# 05pwr_input.net
KiCad netlist of a schematic drawn in Altium Designer
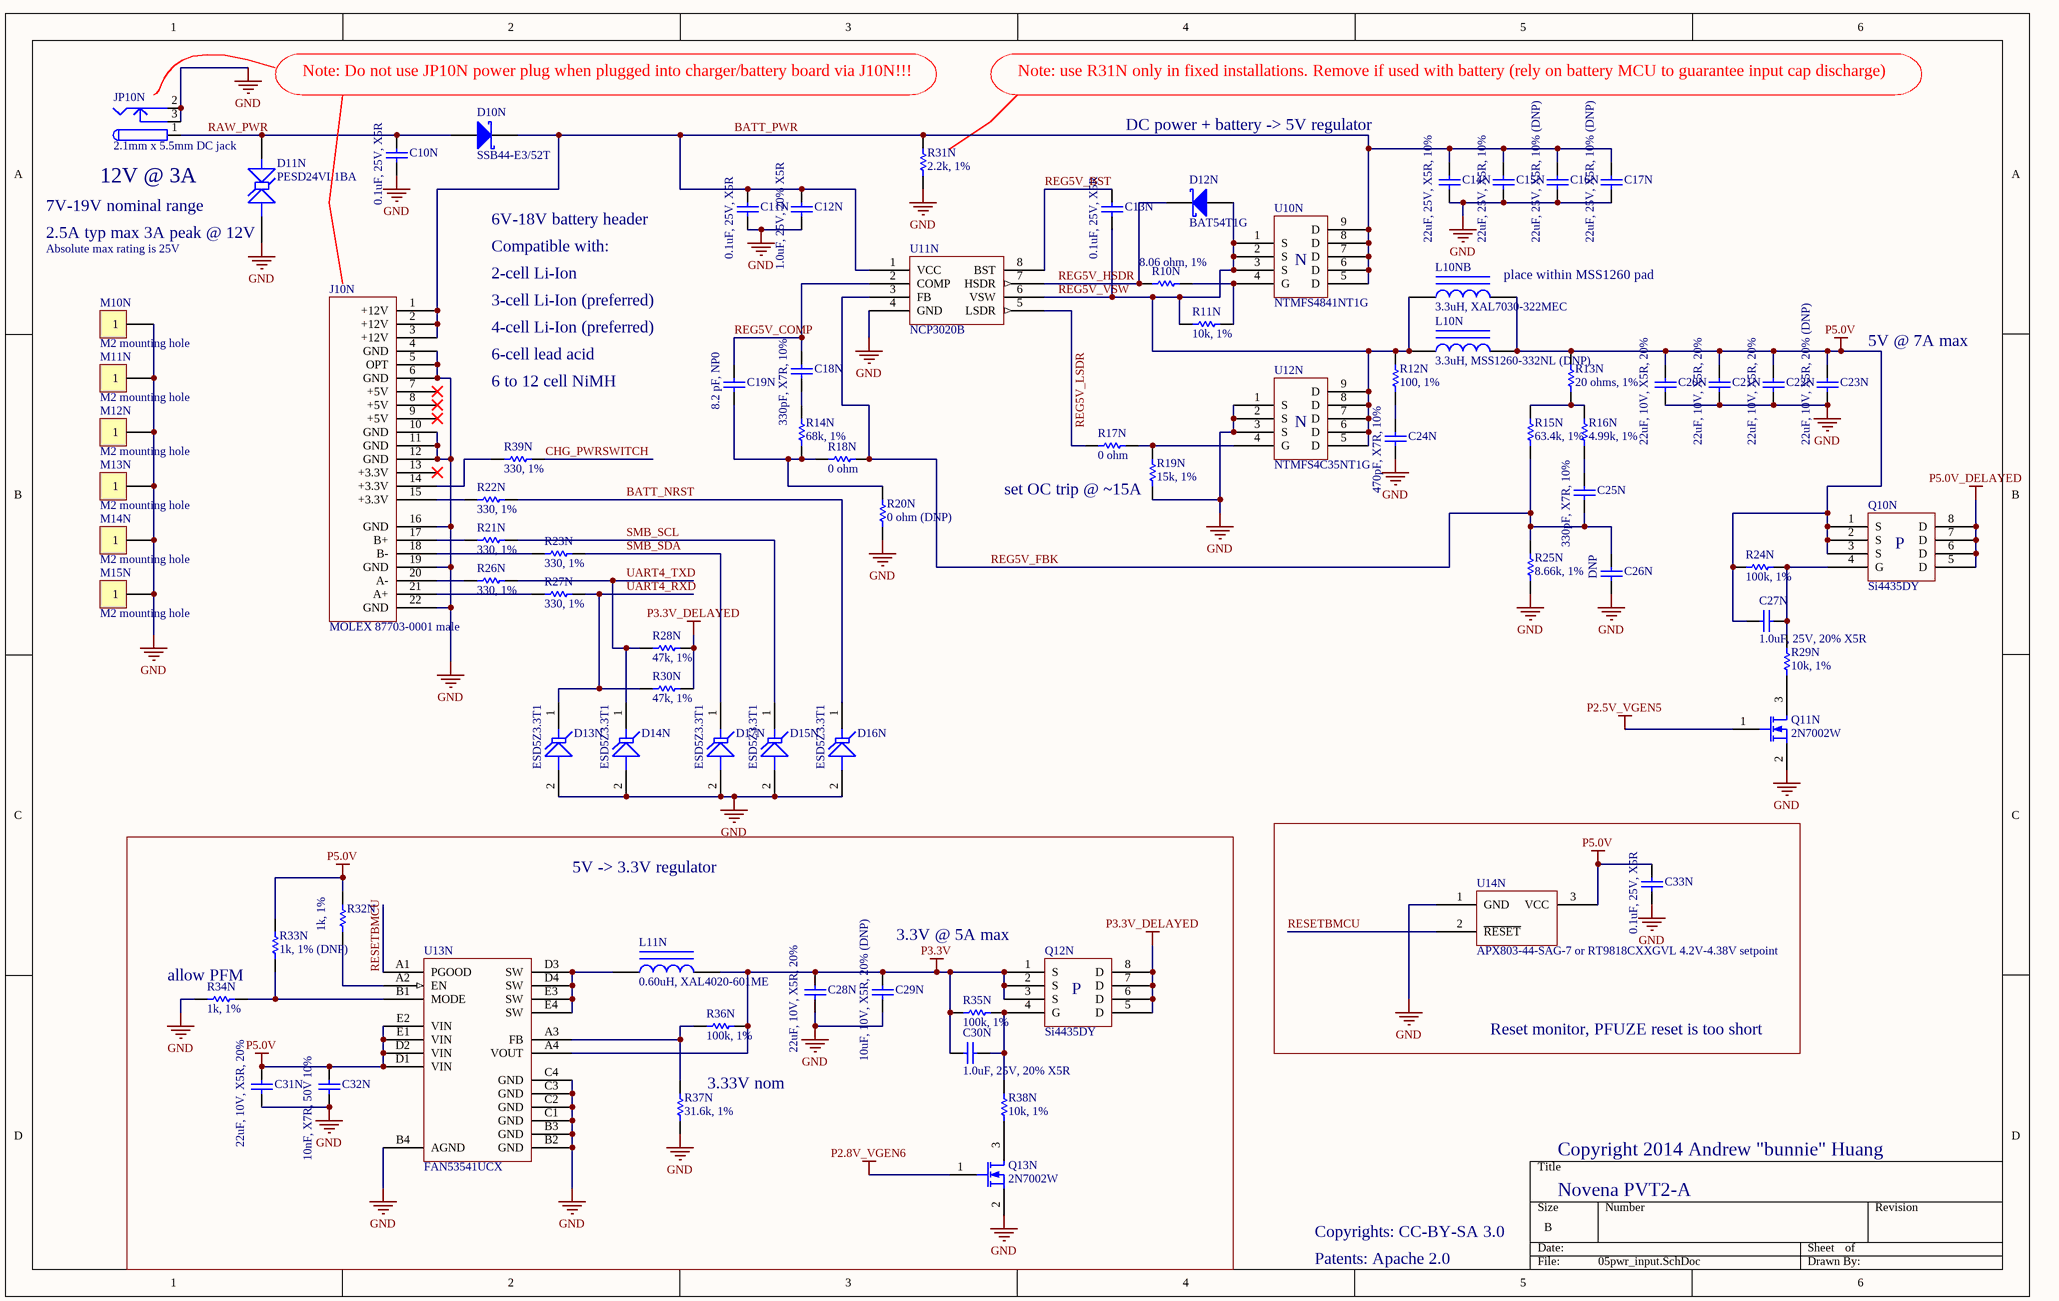
[diagram p0: 05pwr_input.SchDoc]

(export (version "E")
  (design (tool "Eeschema 10.0.6"))
  (components
    (comp (ref "C10N")
      (value "0.1uF, 25V, X5R")
      (footprint "CAPC1005N")
      (description "Capacitor (Semiconductor SIM Model)")
      (fields (field (name "PUBLISHER") "Altium Limited"))
      (libsource (lib "Miscellaneous Devices") (part "Cap Semi"))
    )
    (comp (ref "C11N")
      (value "0.1uF, 25V, X5R")
      (footprint "CAPC1005N")
      (description "Capacitor (Semiconductor SIM Model)")
      (fields (field (name "PUBLISHER") "Altium Limited"))
      (libsource (lib "Miscellaneous Devices") (part "Cap Semi"))
    )
    (comp (ref "C12N")
      (value "1.0uF, 25V, 20% X5R")
      (footprint "CAPC1608N")
      (description "Capacitor (Semiconductor SIM Model)")
      (fields (field (name "PUBLISHER") "Altium Limited"))
      (libsource (lib "Miscellaneous Devices") (part "Cap Semi"))
    )
    (comp (ref "C13N")
      (value "0.1uF, 25V, X5R")
      (footprint "CAPC1005N")
      (description "Capacitor (Semiconductor SIM Model)")
      (fields (field (name "PUBLISHER") "Altium Limited"))
      (libsource (lib "Miscellaneous Devices") (part "Cap Semi"))
    )
    (comp (ref "C14N")
      (value "22uF, 25V, X5R, 10%")
      (footprint "CAPC3225N")
      (description "Capacitor (Semiconductor SIM Model)")
      (fields (field (name "PUBLISHER") "Altium Limited"))
      (libsource (lib "Miscellaneous Devices") (part "Cap Semi"))
    )
    (comp (ref "C15N")
      (value "22uF, 25V, X5R, 10%")
      (footprint "CAPC3225N")
      (description "Capacitor (Semiconductor SIM Model)")
      (fields (field (name "PUBLISHER") "Altium Limited"))
      (libsource (lib "Miscellaneous Devices") (part "Cap Semi"))
    )
    (comp (ref "C16N")
      (value "22uF, 25V, X5R, 10% (DNP)")
      (footprint "CAPC3225N")
      (description "Capacitor (Semiconductor SIM Model)")
      (fields (field (name "PUBLISHER") "Altium Limited"))
      (libsource (lib "Miscellaneous Devices") (part "Cap Semi"))
    )
    (comp (ref "C17N")
      (value "22uF, 25V, X5R, 10% (DNP)")
      (footprint "CAPC3225N")
      (description "Capacitor (Semiconductor SIM Model)")
      (fields (field (name "PUBLISHER") "Altium Limited"))
      (libsource (lib "Miscellaneous Devices") (part "Cap Semi"))
    )
    (comp (ref "C18N")
      (value "330pF, X7R, 10%")
      (footprint "CAPC1005N")
      (description "Capacitor (Semiconductor SIM Model)")
      (fields (field (name "PUBLISHER") "Altium Limited"))
      (libsource (lib "Miscellaneous Devices") (part "Cap Semi"))
    )
    (comp (ref "C19N")
      (value "8.2 pF, NP0")
      (footprint "CAPC1005N")
      (description "Capacitor (Semiconductor SIM Model)")
      (fields (field (name "PUBLISHER") "Altium Limited"))
      (libsource (lib "Miscellaneous Devices") (part "Cap Semi"))
    )
    (comp (ref "C20N")
      (value "22uF, 10V, X5R, 20%")
      (footprint "CAPC2012N")
      (description "Capacitor (Semiconductor SIM Model)")
      (fields (field (name "PUBLISHER") "Altium Limited"))
      (libsource (lib "Miscellaneous Devices") (part "Cap Semi"))
    )
    (comp (ref "C21N")
      (value "22uF, 10V, X5R, 20%")
      (footprint "CAPC2012N")
      (description "Capacitor (Semiconductor SIM Model)")
      (fields (field (name "PUBLISHER") "Altium Limited"))
      (libsource (lib "Miscellaneous Devices") (part "Cap Semi"))
    )
    (comp (ref "C22N")
      (value "22uF, 10V, X5R, 20%")
      (footprint "CAPC2012N")
      (description "Capacitor (Semiconductor SIM Model)")
      (fields (field (name "PUBLISHER") "Altium Limited"))
      (libsource (lib "Miscellaneous Devices") (part "Cap Semi"))
    )
    (comp (ref "C23N")
      (value "22uF, 10V, X5R, 20% (DNP)")
      (footprint "CAPC2012N")
      (description "Capacitor (Semiconductor SIM Model)")
      (fields (field (name "PUBLISHER") "Altium Limited"))
      (libsource (lib "Miscellaneous Devices") (part "Cap Semi"))
    )
    (comp (ref "C24N")
      (value "470pF, X7R, 10%")
      (footprint "CAPC1005N")
      (description "Capacitor (Semiconductor SIM Model)")
      (fields (field (name "PUBLISHER") "Altium Limited"))
      (libsource (lib "Miscellaneous Devices") (part "Cap Semi"))
    )
    (comp (ref "C25N")
      (value "330pF, X7R, 10%")
      (footprint "CAPC1005N")
      (description "Capacitor (Semiconductor SIM Model)")
      (fields (field (name "PUBLISHER") "Altium Limited"))
      (libsource (lib "Miscellaneous Devices") (part "Cap Semi"))
    )
    (comp (ref "C26N")
      (value "DNP")
      (footprint "CAPC1005N")
      (description "Capacitor (Semiconductor SIM Model)")
      (fields (field (name "PUBLISHER") "Altium Limited"))
      (libsource (lib "Miscellaneous Devices") (part "Cap Semi"))
    )
    (comp (ref "C27N")
      (value "1.0uF, 25V, 20% X5R")
      (footprint "CAPC1608N")
      (description "Capacitor (Semiconductor SIM Model)")
      (fields (field (name "PUBLISHER") "Altium Limited"))
      (libsource (lib "Miscellaneous Devices") (part "Cap Semi"))
    )
    (comp (ref "C28N")
      (value "22uF, 10V, X5R, 20%")
      (footprint "CAPC2012N")
      (description "Capacitor (Semiconductor SIM Model)")
      (fields (field (name "PUBLISHER") "Altium Limited"))
      (libsource (lib "Miscellaneous Devices") (part "Cap Semi"))
    )
    (comp (ref "C29N")
      (value "10uF, 10V, X5R, 20% (DNP)")
      (footprint "CAPC1608N")
      (description "Capacitor (Semiconductor SIM Model)")
      (fields (field (name "PUBLISHER") "Altium Limited"))
      (libsource (lib "Miscellaneous Devices") (part "Cap Semi"))
    )
    (comp (ref "C30N")
      (value "1.0uF, 25V, 20% X5R")
      (footprint "CAPC1608N")
      (description "Capacitor (Semiconductor SIM Model)")
      (fields (field (name "PUBLISHER") "Altium Limited"))
      (libsource (lib "Miscellaneous Devices") (part "Cap Semi"))
    )
    (comp (ref "C31N")
      (value "22uF, 10V, X5R, 20%")
      (footprint "CAPC2012N")
      (description "Capacitor (Semiconductor SIM Model)")
      (fields (field (name "PUBLISHER") "Altium Limited"))
      (libsource (lib "Miscellaneous Devices") (part "Cap Semi"))
    )
    (comp (ref "C32N")
      (value "10nF, X7R, 50V 10%")
      (footprint "CAPC1005N")
      (description "Capacitor (Semiconductor SIM Model)")
      (fields (field (name "PUBLISHER") "Altium Limited"))
      (libsource (lib "Miscellaneous Devices") (part "Cap Semi"))
    )
    (comp (ref "C33N")
      (value "0.1uF, 25V, X5R")
      (footprint "CAPC1005N")
      (description "Capacitor (Semiconductor SIM Model)")
      (fields (field (name "PUBLISHER") "Altium Limited"))
      (libsource (lib "Miscellaneous Devices") (part "Cap Semi"))
    )
    (comp (ref "D10N")
      (value "SSB44-E3/52T")
      (footprint "DSO-C2/X2.3")
      (description "Schottky Diode")
      (fields (field (name "PUBLISHER") "Altium Limited"))
      (libsource (lib "Miscellaneous Devices") (part "D Schottky"))
    )
    (comp (ref "D11N")
      (value "PESD24VL1BA")
      (footprint "SOD-323")
      (description "Bidirectional zener diode, Vz 17.1V nom")
      (libsource (lib "commonsch") (part "BIDIR_ESD"))
    )
    (comp (ref "D12N")
      (value "BAT54T1G")
      (footprint "SOD123")
      (description "Schottky Diode")
      (fields (field (name "PUBLISHER") "Altium Limited"))
      (libsource (lib "Miscellaneous Devices") (part "D Schottky"))
    )
    (comp (ref "D13N")
      (value "ESD5Z3.3T1")
      (footprint "SOD-523")
      (description "On Semi 3.3V standoff TVS diode")
      (fields (field (name "PUBLISHER") "Altium Limited"))
      (libsource (lib "Miscellaneous Devices") (part "Tranzorb"))
    )
    (comp (ref "D14N")
      (value "ESD5Z3.3T1")
      (footprint "SOD-523")
      (description "On Semi 3.3V standoff TVS diode")
      (fields (field (name "PUBLISHER") "Altium Limited"))
      (libsource (lib "Miscellaneous Devices") (part "Tranzorb"))
    )
    (comp (ref "D15N")
      (value "ESD5Z3.3T1")
      (footprint "SOD-523")
      (description "On Semi 3.3V standoff TVS diode")
      (fields (field (name "PUBLISHER") "Altium Limited"))
      (libsource (lib "Miscellaneous Devices") (part "Tranzorb"))
    )
    (comp (ref "D16N")
      (value "ESD5Z3.3T1")
      (footprint "SOD-523")
      (description "On Semi 3.3V standoff TVS diode")
      (fields (field (name "PUBLISHER") "Altium Limited"))
      (libsource (lib "Miscellaneous Devices") (part "Tranzorb"))
    )
    (comp (ref "D17N")
      (value "ESD5Z3.3T1")
      (footprint "SOD-523")
      (description "On Semi 3.3V standoff TVS diode")
      (fields (field (name "PUBLISHER") "Altium Limited"))
      (libsource (lib "Miscellaneous Devices") (part "Tranzorb"))
    )
    (comp (ref "J10N")
      (value "MOLEX 87703-0001 male")
      (footprint "SATA_MOLEX-87703-0001")
      (description "SATA+Power connector")
      (libsource (lib "commonsch") (part "SATA_22P_HEADER"))
    )
    (comp (ref "JP10N")
      (value "2.1mm x 5.5mm DC jack")
      (footprint "CUI_PJ_002AH_SMT")
      (description "Low Voltage Power Supply Connector")
      (fields (field (name "PUBLISHER") "Altium Limited"))
      (libsource (lib "Miscellaneous Connectors") (part "PWR2.5"))
    )
    (comp (ref "L10N")
      (value "3.3uH, MSS1260-332NL (DNP)")
      (footprint "COILCRAFT_MSS1048")
      (description "Magnetic-Core Inductor")
      (fields (field (name "PUBLISHER") "Altium Limited"))
      (libsource (lib "Miscellaneous Devices") (part "Inductor Iron"))
    )
    (comp (ref "L10NB")
      (value "3.3uH, XAL7030-322MEC")
      (footprint "COILCRAFT_XAL7030")
      (description "Magnetic-Core Inductor")
      (fields (field (name "PUBLISHER") "Altium Limited"))
      (libsource (lib "Miscellaneous Devices") (part "Inductor Iron"))
    )
    (comp (ref "L11N")
      (value "0.60uH, XAL4020-601ME")
      (footprint "COILCRAFT_XAL4020")
      (description "Magnetic-Core Inductor")
      (fields (field (name "PUBLISHER") "Altium Limited"))
      (libsource (lib "Miscellaneous Devices") (part "Inductor Iron"))
    )
    (comp (ref "M10N")
      (value "M2 mounting hole")
      (footprint "HOLE_M2_MOUNT")
      (description "Connector")
      (libsource (lib "*") (part "CON1"))
    )
    (comp (ref "M11N")
      (value "M2 mounting hole")
      (footprint "HOLE_M2_MOUNT")
      (description "Connector")
      (libsource (lib "*") (part "CON1"))
    )
    (comp (ref "M12N")
      (value "M2 mounting hole")
      (footprint "HOLE_M2_MOUNT")
      (description "Connector")
      (libsource (lib "*") (part "CON1"))
    )
    (comp (ref "M13N")
      (value "M2 mounting hole")
      (footprint "HOLE_M2_MOUNT")
      (description "Connector")
      (libsource (lib "*") (part "CON1"))
    )
    (comp (ref "M14N")
      (value "M2 mounting hole")
      (footprint "HOLE_M2_MOUNT")
      (description "Connector")
      (libsource (lib "*") (part "CON1"))
    )
    (comp (ref "M15N")
      (value "M2 mounting hole")
      (footprint "HOLE_M2_MOUNT")
      (description "Connector")
      (libsource (lib "*") (part "CON1"))
    )
    (comp (ref "Q10N")
      (value "Si4435DY")
      (footprint "SOIC127P600-8AN")
      (description "Singre P-channel FET, 8A, 30V")
      (libsource (lib "commonsch") (part "Si4435DY"))
    )
    (comp (ref "Q11N")
      (value "2N7002W")
      (footprint "SOT323-3AN")
      (description "N-Channel MOSFET")
      (fields (field (name "PUBLISHER") "Altium Limited"))
      (libsource (lib "Miscellaneous Devices") (part "MOSFET-N"))
    )
    (comp (ref "Q12N")
      (value "Si4435DY")
      (footprint "SOIC127P600-8AN")
      (description "Singre P-channel FET, 8A, 30V")
      (libsource (lib "commonsch") (part "Si4435DY"))
    )
    (comp (ref "Q13N")
      (value "2N7002W")
      (footprint "SOT323-3AN")
      (description "N-Channel MOSFET")
      (fields (field (name "PUBLISHER") "Altium Limited"))
      (libsource (lib "Miscellaneous Devices") (part "MOSFET-N"))
    )
    (comp (ref "R10N")
      (value "8.06 ohm, 1%")
      (footprint "RESC1005N")
      (description "Resistor")
      (fields (field (name "PUBLISHER") "Altium Limited"))
      (libsource (lib "Miscellaneous Devices") (part "Res1"))
    )
    (comp (ref "R11N")
      (value "10k, 1%")
      (footprint "RESC1005N")
      (description "Resistor")
      (fields (field (name "PUBLISHER") "Altium Limited"))
      (libsource (lib "Miscellaneous Devices") (part "Res1"))
    )
    (comp (ref "R12N")
      (value "100, 1%")
      (footprint "RESC1005N")
      (description "Resistor")
      (fields (field (name "PUBLISHER") "Altium Limited"))
      (libsource (lib "Miscellaneous Devices") (part "Res1"))
    )
    (comp (ref "R13N")
      (value "20 ohms, 1%")
      (footprint "RESC1005N")
      (description "Resistor")
      (fields (field (name "PUBLISHER") "Altium Limited"))
      (libsource (lib "Miscellaneous Devices") (part "Res1"))
    )
    (comp (ref "R14N")
      (value "68k, 1%")
      (footprint "RESC1005N")
      (description "Resistor")
      (fields (field (name "PUBLISHER") "Altium Limited"))
      (libsource (lib "Miscellaneous Devices") (part "Res1"))
    )
    (comp (ref "R15N")
      (value "63.4k, 1%")
      (footprint "RESC1005N")
      (description "Resistor")
      (fields (field (name "PUBLISHER") "Altium Limited"))
      (libsource (lib "Miscellaneous Devices") (part "Res1"))
    )
    (comp (ref "R16N")
      (value "4.99k, 1%")
      (footprint "RESC1005N")
      (description "Resistor")
      (fields (field (name "PUBLISHER") "Altium Limited"))
      (libsource (lib "Miscellaneous Devices") (part "Res1"))
    )
    (comp (ref "R17N")
      (value "0 ohm")
      (footprint "RESC1005N")
      (description "Resistor")
      (fields (field (name "PUBLISHER") "Altium Limited"))
      (libsource (lib "Miscellaneous Devices") (part "Res1"))
    )
    (comp (ref "R18N")
      (value "0 ohm")
      (footprint "RESC1005N")
      (description "Resistor")
      (fields (field (name "PUBLISHER") "Altium Limited"))
      (libsource (lib "Miscellaneous Devices") (part "Res1"))
    )
    (comp (ref "R19N")
      (value "15k, 1%")
      (footprint "RESC1005N")
      (description "Resistor")
      (fields (field (name "PUBLISHER") "Altium Limited"))
      (libsource (lib "Miscellaneous Devices") (part "Res1"))
    )
    (comp (ref "R20N")
      (value "0 ohm (DNP)")
      (footprint "RESC1005N")
      (description "Resistor")
      (fields (field (name "PUBLISHER") "Altium Limited"))
      (libsource (lib "Miscellaneous Devices") (part "Res1"))
    )
    (comp (ref "R21N")
      (value "330, 1%")
      (footprint "RESC1005N")
      (description "Resistor")
      (fields (field (name "PUBLISHER") "Altium Limited"))
      (libsource (lib "Miscellaneous Devices") (part "Res1"))
    )
    (comp (ref "R22N")
      (value "330, 1%")
      (footprint "RESC1005N")
      (description "Resistor")
      (fields (field (name "PUBLISHER") "Altium Limited"))
      (libsource (lib "Miscellaneous Devices") (part "Res1"))
    )
    (comp (ref "R23N")
      (value "330, 1%")
      (footprint "RESC1005N")
      (description "Resistor")
      (fields (field (name "PUBLISHER") "Altium Limited"))
      (libsource (lib "Miscellaneous Devices") (part "Res1"))
    )
    (comp (ref "R24N")
      (value "100k, 1%")
      (footprint "RESC1005N")
      (description "Resistor")
      (fields (field (name "PUBLISHER") "Altium Limited"))
      (libsource (lib "Miscellaneous Devices") (part "Res1"))
    )
    (comp (ref "R25N")
      (value "8.66k, 1%")
      (footprint "RESC1005N")
      (description "Resistor")
      (fields (field (name "PUBLISHER") "Altium Limited"))
      (libsource (lib "Miscellaneous Devices") (part "Res1"))
    )
    (comp (ref "R26N")
      (value "330, 1%")
      (footprint "RESC1005N")
      (description "Resistor")
      (fields (field (name "PUBLISHER") "Altium Limited"))
      (libsource (lib "Miscellaneous Devices") (part "Res1"))
    )
    (comp (ref "R27N")
      (value "330, 1%")
      (footprint "RESC1005N")
      (description "Resistor")
      (fields (field (name "PUBLISHER") "Altium Limited"))
      (libsource (lib "Miscellaneous Devices") (part "Res1"))
    )
    (comp (ref "R28N")
      (value "47k, 1%")
      (footprint "RESC1005N")
      (description "Resistor")
      (fields (field (name "PUBLISHER") "Altium Limited"))
      (libsource (lib "Miscellaneous Devices") (part "Res1"))
    )
    (comp (ref "R29N")
      (value "10k, 1%")
      (footprint "RESC1005N")
      (description "Resistor")
      (fields (field (name "PUBLISHER") "Altium Limited"))
      (libsource (lib "Miscellaneous Devices") (part "Res1"))
    )
    (comp (ref "R30N")
      (value "47k, 1%")
      (footprint "RESC1005N")
      (description "Resistor")
      (fields (field (name "PUBLISHER") "Altium Limited"))
      (libsource (lib "Miscellaneous Devices") (part "Res1"))
    )
    (comp (ref "R31N")
      (value "2.2k, 1%")
      (footprint "RESC1005N")
      (description "Resistor")
      (fields (field (name "PUBLISHER") "Altium Limited"))
      (libsource (lib "Miscellaneous Devices") (part "Res1"))
    )
    (comp (ref "R32N")
      (value "1k, 1%")
      (footprint "RESC1005N")
      (description "Resistor")
      (fields (field (name "PUBLISHER") "Altium Limited"))
      (libsource (lib "Miscellaneous Devices") (part "Res1"))
    )
    (comp (ref "R33N")
      (value "1k, 1% (DNP)")
      (footprint "RESC1005N")
      (description "Resistor")
      (fields (field (name "PUBLISHER") "Altium Limited"))
      (libsource (lib "Miscellaneous Devices") (part "Res1"))
    )
    (comp (ref "R34N")
      (value "1k, 1%")
      (footprint "RESC1005N")
      (description "Resistor")
      (fields (field (name "PUBLISHER") "Altium Limited"))
      (libsource (lib "Miscellaneous Devices") (part "Res1"))
    )
    (comp (ref "R35N")
      (value "100k, 1%")
      (footprint "RESC1005N")
      (description "Resistor")
      (fields (field (name "PUBLISHER") "Altium Limited"))
      (libsource (lib "Miscellaneous Devices") (part "Res1"))
    )
    (comp (ref "R36N")
      (value "100k, 1%")
      (footprint "RESC1005N")
      (description "Resistor")
      (fields (field (name "PUBLISHER") "Altium Limited"))
      (libsource (lib "Miscellaneous Devices") (part "Res1"))
    )
    (comp (ref "R37N")
      (value "31.6k, 1%")
      (footprint "RESC1005N")
      (description "Resistor")
      (fields (field (name "PUBLISHER") "Altium Limited"))
      (libsource (lib "Miscellaneous Devices") (part "Res1"))
    )
    (comp (ref "R38N")
      (value "10k, 1%")
      (footprint "RESC1005N")
      (description "Resistor")
      (fields (field (name "PUBLISHER") "Altium Limited"))
      (libsource (lib "Miscellaneous Devices") (part "Res1"))
    )
    (comp (ref "R39N")
      (value "330, 1%")
      (footprint "RESC1005N")
      (description "Resistor")
      (fields (field (name "PUBLISHER") "Altium Limited"))
      (libsource (lib "Miscellaneous Devices") (part "Res1"))
    )
    (comp (ref "U10N")
      (value "NTMFS4841NT1G")
      (footprint "ONSEMI_DFN5_5x6_1.27P")
      (description "N channel power MOSFET, 30V, 57A SO-8FL")
      (libsource (lib "commonsch") (part "NTMFS4841N"))
    )
    (comp (ref "U11N")
      (value "NCP3020B")
      (footprint "SOIC127P600-8AN")
      (description "Synchronous PWM controller, 4.7-28V in, 0.6V ref")
      (libsource (lib "commonsch") (part "NCP3020B"))
    )
    (comp (ref "U12N")
      (value "NTMFS4C35NT1G")
      (footprint "ONSEMI_DFN5_5x6_1.27P")
      (description "N channel power MOSFET, 30V, 57A SO-8FL")
      (libsource (lib "commonsch") (part "NTMFS4841N"))
    )
    (comp (ref "U13N")
      (value "FAN53541UCX")
      (footprint "FAIRCHILD_WLCSP_BGA100P9X9-81A")
      (description "2.4MHz 5A Sync buck regulator, integrated FET")
      (libsource (lib "commonsch") (part "FAN53540UCX"))
    )
    (comp (ref "U14N")
      (value "APX803-44-SAG-7 or RT9818CXXGVL 4.2V-4.38V setpoint")
      (footprint "SOT23-3N")
      (description "Reset monitor. Voltage specified by XX in P/N. Multiple vendors.")
      (libsource (lib "commonsch") (part "RESET_SOT23"))
    )
  )
  (nets
    (net (code "1") (name "/BATT_NRST") (class "Default")
      (node (ref "D16N") (pin "1") (pinfunction "K_1") (pintype "passive"))
      (node (ref "R22N") (pin "2") (pinfunction "2_2") (pintype "passive"))
    )
    (net (code "2") (name "/BATT_PWR") (class "Default")
      (node (ref "C11N") (pin "1") (pinfunction "1_1") (pintype "passive"))
      (node (ref "C12N") (pin "1") (pinfunction "1_1") (pintype "passive"))
      (node (ref "C14N") (pin "1") (pinfunction "1_1") (pintype "passive"))
      (node (ref "C15N") (pin "1") (pinfunction "1_1") (pintype "passive"))
      (node (ref "C16N") (pin "1") (pinfunction "1_1") (pintype "passive"))
      (node (ref "C17N") (pin "1") (pinfunction "1_1") (pintype "passive"))
      (node (ref "D10N") (pin "2") (pinfunction "K_2") (pintype "passive"))
      (node (ref "J10N") (pin "1") (pinfunction "+12V_1") (pintype "power_in"))
      (node (ref "J10N") (pin "2") (pinfunction "+12V_2") (pintype "power_in"))
      (node (ref "J10N") (pin "3") (pinfunction "+12V_3") (pintype "power_in"))
      (node (ref "R31N") (pin "2") (pinfunction "2_2") (pintype "passive"))
      (node (ref "U10N") (pin "5") (pinfunction "D_5") (pintype "passive"))
      (node (ref "U10N") (pin "6") (pinfunction "D_6") (pintype "passive"))
      (node (ref "U10N") (pin "7") (pinfunction "D_7") (pintype "passive"))
      (node (ref "U10N") (pin "8") (pinfunction "D_8") (pintype "passive"))
      (node (ref "U10N") (pin "9") (pinfunction "D_9") (pintype "passive"))
      (node (ref "U11N") (pin "1") (pinfunction "VCC_1") (pintype "power_in"))
    )
    (net (code "3") (name "/CHG_PWRSWITCH") (class "Default")
      (node (ref "R39N") (pin "2") (pinfunction "2_2") (pintype "passive"))
    )
    (net (code "4") (name "/RAW_PWR") (class "Default")
      (node (ref "C10N") (pin "1") (pinfunction "1_1") (pintype "passive"))
      (node (ref "D10N") (pin "1") (pinfunction "A_1") (pintype "passive"))
      (node (ref "D11N") (pin "2") (pinfunction "K_2") (pintype "passive"))
      (node (ref "JP10N") (pin "1") (pintype "power_in"))
    )
    (net (code "5") (name "/REG5V_BST") (class "Default")
      (node (ref "C13N") (pin "1") (pinfunction "1_1") (pintype "passive"))
      (node (ref "U11N") (pin "8") (pinfunction "BST_8") (pintype "passive"))
    )
    (net (code "6") (name "/REG5V_COMP") (class "Default")
      (node (ref "C18N") (pin "1") (pinfunction "1_1") (pintype "passive"))
      (node (ref "C19N") (pin "1") (pinfunction "1_1") (pintype "passive"))
      (node (ref "U11N") (pin "2") (pinfunction "COMP_2") (pintype "passive"))
    )
    (net (code "7") (name "/REG5V_FBK") (class "Default")
      (node (ref "C25N") (pin "2") (pinfunction "2_2") (pintype "passive"))
      (node (ref "C26N") (pin "1") (pinfunction "1_1") (pintype "passive"))
      (node (ref "R15N") (pin "1") (pinfunction "1_1") (pintype "passive"))
      (node (ref "R18N") (pin "2") (pinfunction "2_2") (pintype "passive"))
      (node (ref "R25N") (pin "2") (pinfunction "2_2") (pintype "passive"))
      (node (ref "U11N") (pin "3") (pinfunction "FB_3") (pintype "passive"))
    )
    (net (code "8") (name "/REG5V_HSDR") (class "Default")
      (node (ref "D12N") (pin "2") (pinfunction "K_2") (pintype "passive"))
      (node (ref "R10N") (pin "1") (pinfunction "1_1") (pintype "passive"))
      (node (ref "U11N") (pin "7") (pinfunction "HSDR_7") (pintype "output"))
    )
    (net (code "9") (name "/REG5V_LSDR") (class "Default")
      (node (ref "R17N") (pin "1") (pinfunction "1_1") (pintype "passive"))
      (node (ref "U11N") (pin "5") (pinfunction "LSDR_5") (pintype "output"))
    )
    (net (code "10") (name "/REG5V_VSW") (class "Default")
      (node (ref "C13N") (pin "2") (pinfunction "2_2") (pintype "passive"))
      (node (ref "D12N") (pin "1") (pinfunction "A_1") (pintype "passive"))
      (node (ref "L10N") (pin "1") (pinfunction "1_1") (pintype "passive"))
      (node (ref "L10NB") (pin "1") (pinfunction "1_1") (pintype "passive"))
      (node (ref "R11N") (pin "2") (pinfunction "2_2") (pintype "passive"))
      (node (ref "R12N") (pin "2") (pinfunction "2_2") (pintype "passive"))
      (node (ref "U10N") (pin "1") (pinfunction "S_1") (pintype "passive"))
      (node (ref "U10N") (pin "2") (pinfunction "S_2") (pintype "passive"))
      (node (ref "U10N") (pin "3") (pinfunction "S_3") (pintype "passive"))
      (node (ref "U11N") (pin "6") (pinfunction "VSW_6") (pintype "passive"))
      (node (ref "U12N") (pin "5") (pinfunction "D_5") (pintype "passive"))
      (node (ref "U12N") (pin "6") (pinfunction "D_6") (pintype "passive"))
      (node (ref "U12N") (pin "7") (pinfunction "D_7") (pintype "passive"))
      (node (ref "U12N") (pin "8") (pinfunction "D_8") (pintype "passive"))
      (node (ref "U12N") (pin "9") (pinfunction "D_9") (pintype "passive"))
    )
    (net (code "11") (name "/RESETBMCU") (class "Default")
      (node (ref "U13N") (pin "A1") (pinfunction "PGOOD_A1") (pintype "open_collector"))
      (node (ref "U14N") (pin "2") (pinfunction "~{RESET}_2") (pintype "open_collector"))
    )
    (net (code "12") (name "/SMB_SCL") (class "Default")
      (node (ref "D15N") (pin "1") (pinfunction "K_1") (pintype "passive"))
      (node (ref "R21N") (pin "1") (pinfunction "1_1") (pintype "passive"))
    )
    (net (code "13") (name "/SMB_SDA") (class "Default")
      (node (ref "D17N") (pin "1") (pinfunction "K_1") (pintype "passive"))
      (node (ref "R23N") (pin "2") (pinfunction "2_2") (pintype "passive"))
    )
    (net (code "14") (name "/UART4_RXD") (class "Default")
      (node (ref "D13N") (pin "1") (pinfunction "K_1") (pintype "passive"))
      (node (ref "R27N") (pin "2") (pinfunction "2_2") (pintype "passive"))
      (node (ref "R30N") (pin "2") (pinfunction "2_2") (pintype "passive"))
    )
    (net (code "15") (name "/UART4_TXD") (class "Default")
      (node (ref "D14N") (pin "1") (pinfunction "K_1") (pintype "passive"))
      (node (ref "R26N") (pin "2") (pinfunction "2_2") (pintype "passive"))
      (node (ref "R28N") (pin "2") (pinfunction "2_2") (pintype "passive"))
    )
    (net (code "16") (name "GND") (class "Default")
      (node (ref "C10N") (pin "2") (pinfunction "2_2") (pintype "passive"))
      (node (ref "C11N") (pin "2") (pinfunction "2_2") (pintype "passive"))
      (node (ref "C12N") (pin "2") (pinfunction "2_2") (pintype "passive"))
      (node (ref "C14N") (pin "2") (pinfunction "2_2") (pintype "passive"))
      (node (ref "C15N") (pin "2") (pinfunction "2_2") (pintype "passive"))
      (node (ref "C16N") (pin "2") (pinfunction "2_2") (pintype "passive"))
      (node (ref "C17N") (pin "2") (pinfunction "2_2") (pintype "passive"))
      (node (ref "C20N") (pin "2") (pinfunction "2_2") (pintype "passive"))
      (node (ref "C21N") (pin "2") (pinfunction "2_2") (pintype "passive"))
      (node (ref "C22N") (pin "2") (pinfunction "2_2") (pintype "passive"))
      (node (ref "C23N") (pin "2") (pinfunction "2_2") (pintype "passive"))
      (node (ref "C24N") (pin "2") (pinfunction "2_2") (pintype "passive"))
      (node (ref "C26N") (pin "2") (pinfunction "2_2") (pintype "passive"))
      (node (ref "C28N") (pin "2") (pinfunction "2_2") (pintype "passive"))
      (node (ref "C29N") (pin "2") (pinfunction "2_2") (pintype "passive"))
      (node (ref "C31N") (pin "2") (pinfunction "2_2") (pintype "passive"))
      (node (ref "C32N") (pin "2") (pinfunction "2_2") (pintype "passive"))
      (node (ref "C33N") (pin "2") (pinfunction "2_2") (pintype "passive"))
      (node (ref "D11N") (pin "1") (pinfunction "A_1") (pintype "passive"))
      (node (ref "D13N") (pin "2") (pinfunction "A_2") (pintype "passive"))
      (node (ref "D14N") (pin "2") (pinfunction "A_2") (pintype "passive"))
      (node (ref "D15N") (pin "2") (pinfunction "A_2") (pintype "passive"))
      (node (ref "D16N") (pin "2") (pinfunction "A_2") (pintype "passive"))
      (node (ref "D17N") (pin "2") (pinfunction "A_2") (pintype "passive"))
      (node (ref "J10N") (pin "10") (pinfunction "GND_10") (pintype "power_in"))
      (node (ref "J10N") (pin "11") (pinfunction "GND_11") (pintype "power_in"))
      (node (ref "J10N") (pin "12") (pinfunction "GND_12") (pintype "power_in"))
      (node (ref "J10N") (pin "16") (pinfunction "GND_16") (pintype "power_in"))
      (node (ref "J10N") (pin "19") (pinfunction "GND_19") (pintype "power_in"))
      (node (ref "J10N") (pin "22") (pinfunction "GND_22") (pintype "power_in"))
      (node (ref "J10N") (pin "4") (pinfunction "GND_4") (pintype "power_in"))
      (node (ref "J10N") (pin "5") (pinfunction "OPT_5") (pintype "passive"))
      (node (ref "J10N") (pin "6") (pinfunction "GND_6") (pintype "power_in"))
      (node (ref "JP10N") (pin "2") (pintype "power_in"))
      (node (ref "JP10N") (pin "3") (pintype "power_in"))
      (node (ref "M10N") (pin "1") (pinfunction "1_1") (pintype "passive"))
      (node (ref "M11N") (pin "1") (pinfunction "1_1") (pintype "passive"))
      (node (ref "M12N") (pin "1") (pinfunction "1_1") (pintype "passive"))
      (node (ref "M13N") (pin "1") (pinfunction "1_1") (pintype "passive"))
      (node (ref "M14N") (pin "1") (pinfunction "1_1") (pintype "passive"))
      (node (ref "M15N") (pin "1") (pinfunction "1_1") (pintype "passive"))
      (node (ref "Q11N") (pin "2") (pinfunction "S_2") (pintype "passive"))
      (node (ref "Q13N") (pin "2") (pinfunction "S_2") (pintype "passive"))
      (node (ref "R19N") (pin "1") (pinfunction "1_1") (pintype "passive"))
      (node (ref "R20N") (pin "1") (pinfunction "1_1") (pintype "passive"))
      (node (ref "R25N") (pin "1") (pinfunction "1_1") (pintype "passive"))
      (node (ref "R31N") (pin "1") (pinfunction "1_1") (pintype "passive"))
      (node (ref "R34N") (pin "2") (pinfunction "2_2") (pintype "passive"))
      (node (ref "R37N") (pin "1") (pinfunction "1_1") (pintype "passive"))
      (node (ref "U11N") (pin "4") (pinfunction "GND_4") (pintype "power_in"))
      (node (ref "U12N") (pin "1") (pinfunction "S_1") (pintype "passive"))
      (node (ref "U12N") (pin "2") (pinfunction "S_2") (pintype "passive"))
      (node (ref "U12N") (pin "3") (pinfunction "S_3") (pintype "passive"))
      (node (ref "U13N") (pin "B2") (pinfunction "GND_B2") (pintype "power_in"))
      (node (ref "U13N") (pin "B3") (pinfunction "GND_B3") (pintype "power_in"))
      (node (ref "U13N") (pin "B4") (pinfunction "AGND_B4") (pintype "power_in"))
      (node (ref "U13N") (pin "C1") (pinfunction "GND_C1") (pintype "power_in"))
      (node (ref "U13N") (pin "C2") (pinfunction "GND_C2") (pintype "power_in"))
      (node (ref "U13N") (pin "C3") (pinfunction "GND_C3") (pintype "power_in"))
      (node (ref "U13N") (pin "C4") (pinfunction "GND_C4") (pintype "power_in"))
      (node (ref "U14N") (pin "1") (pinfunction "GND_1") (pintype "power_in"))
    )
    (net (code "17") (name "Net-(C18N-Pad2)") (class "Default")
      (node (ref "C18N") (pin "2") (pinfunction "2_2") (pintype "passive"))
      (node (ref "R14N") (pin "2") (pinfunction "2_2") (pintype "passive"))
    )
    (net (code "18") (name "Net-(C19N-Pad2)") (class "Default")
      (node (ref "C19N") (pin "2") (pinfunction "2_2") (pintype "passive"))
      (node (ref "R14N") (pin "1") (pinfunction "1_1") (pintype "passive"))
      (node (ref "R18N") (pin "1") (pinfunction "1_1") (pintype "passive"))
      (node (ref "R20N") (pin "2") (pinfunction "2_2") (pintype "passive"))
    )
    (net (code "19") (name "Net-(C24N-Pad1)") (class "Default")
      (node (ref "C24N") (pin "1") (pinfunction "1_1") (pintype "passive"))
      (node (ref "R12N") (pin "1") (pinfunction "1_1") (pintype "passive"))
    )
    (net (code "20") (name "Net-(C25N-Pad1)") (class "Default")
      (node (ref "C25N") (pin "1") (pinfunction "1_1") (pintype "passive"))
      (node (ref "R16N") (pin "1") (pinfunction "1_1") (pintype "passive"))
    )
    (net (code "21") (name "Net-(J10N-+3.3V-Pad14)") (class "Default")
      (node (ref "J10N") (pin "14") (pinfunction "+3.3V_14") (pintype "power_in"))
      (node (ref "R39N") (pin "1") (pinfunction "1_1") (pintype "passive"))
    )
    (net (code "22") (name "Net-(J10N-+3.3V-Pad15)") (class "Default")
      (node (ref "J10N") (pin "15") (pinfunction "+3.3V_15") (pintype "power_in"))
      (node (ref "R22N") (pin "1") (pinfunction "1_1") (pintype "passive"))
    )
    (net (code "23") (name "Net-(J10N-A+)") (class "Default")
      (node (ref "J10N") (pin "21") (pinfunction "A+_21") (pintype "passive"))
      (node (ref "R27N") (pin "1") (pinfunction "1_1") (pintype "passive"))
    )
    (net (code "24") (name "Net-(J10N-A-)") (class "Default")
      (node (ref "J10N") (pin "20") (pinfunction "A-_20") (pintype "passive"))
      (node (ref "R26N") (pin "1") (pinfunction "1_1") (pintype "passive"))
    )
    (net (code "25") (name "Net-(J10N-B+)") (class "Default")
      (node (ref "J10N") (pin "17") (pinfunction "B+_17") (pintype "passive"))
      (node (ref "R21N") (pin "2") (pinfunction "2_2") (pintype "passive"))
    )
    (net (code "26") (name "Net-(J10N-B-)") (class "Default")
      (node (ref "J10N") (pin "18") (pinfunction "B-_18") (pintype "passive"))
      (node (ref "R23N") (pin "1") (pinfunction "1_1") (pintype "passive"))
    )
    (net (code "27") (name "Net-(L11N-Pad1)") (class "Default")
      (node (ref "L11N") (pin "1") (pinfunction "1_1") (pintype "passive"))
      (node (ref "U13N") (pin "D3") (pinfunction "SW_D3") (pintype "passive"))
      (node (ref "U13N") (pin "D4") (pinfunction "SW_D4") (pintype "passive"))
      (node (ref "U13N") (pin "E3") (pinfunction "SW_E3") (pintype "passive"))
      (node (ref "U13N") (pin "E4") (pinfunction "SW_E4") (pintype "passive"))
    )
    (net (code "28") (name "Net-(Q10N-G)") (class "Default")
      (node (ref "C27N") (pin "2") (pinfunction "2_2") (pintype "passive"))
      (node (ref "Q10N") (pin "4") (pinfunction "G_4") (pintype "passive"))
      (node (ref "R24N") (pin "1") (pinfunction "1_1") (pintype "passive"))
      (node (ref "R29N") (pin "1") (pinfunction "1_1") (pintype "passive"))
    )
    (net (code "29") (name "Net-(Q11N-D)") (class "Default")
      (node (ref "Q11N") (pin "3") (pinfunction "D_3") (pintype "passive"))
      (node (ref "R29N") (pin "2") (pinfunction "2_2") (pintype "passive"))
    )
    (net (code "30") (name "Net-(Q12N-G)") (class "Default")
      (node (ref "C30N") (pin "2") (pinfunction "2_2") (pintype "passive"))
      (node (ref "Q12N") (pin "4") (pinfunction "G_4") (pintype "passive"))
      (node (ref "R35N") (pin "1") (pinfunction "1_1") (pintype "passive"))
      (node (ref "R38N") (pin "1") (pinfunction "1_1") (pintype "passive"))
    )
    (net (code "31") (name "Net-(Q13N-D)") (class "Default")
      (node (ref "Q13N") (pin "3") (pinfunction "D_3") (pintype "passive"))
      (node (ref "R38N") (pin "2") (pinfunction "2_2") (pintype "passive"))
    )
    (net (code "32") (name "Net-(R13N-Pad1)") (class "Default")
      (node (ref "R13N") (pin "1") (pinfunction "1_1") (pintype "passive"))
      (node (ref "R15N") (pin "2") (pinfunction "2_2") (pintype "passive"))
      (node (ref "R16N") (pin "2") (pinfunction "2_2") (pintype "passive"))
    )
    (net (code "33") (name "Net-(U10N-G)") (class "Default")
      (node (ref "R10N") (pin "2") (pinfunction "2_2") (pintype "passive"))
      (node (ref "R11N") (pin "1") (pinfunction "1_1") (pintype "passive"))
      (node (ref "U10N") (pin "4") (pinfunction "G_4") (pintype "passive"))
    )
    (net (code "34") (name "Net-(U12N-G)") (class "Default")
      (node (ref "R17N") (pin "2") (pinfunction "2_2") (pintype "passive"))
      (node (ref "R19N") (pin "2") (pinfunction "2_2") (pintype "passive"))
      (node (ref "U12N") (pin "4") (pinfunction "G_4") (pintype "passive"))
    )
    (net (code "35") (name "Net-(U13N-EN)") (class "Default")
      (node (ref "R32N") (pin "2") (pinfunction "2_2") (pintype "passive"))
      (node (ref "U13N") (pin "A2") (pinfunction "EN_A2") (pintype "input"))
    )
    (net (code "36") (name "Net-(U13N-FB)") (class "Default")
      (node (ref "R36N") (pin "2") (pinfunction "2_2") (pintype "passive"))
      (node (ref "R37N") (pin "2") (pinfunction "2_2") (pintype "passive"))
      (node (ref "U13N") (pin "A3") (pinfunction "FB_A3") (pintype "passive"))
    )
    (net (code "37") (name "Net-(U13N-MODE)") (class "Default")
      (node (ref "R33N") (pin "1") (pinfunction "1_1") (pintype "passive"))
      (node (ref "R34N") (pin "1") (pinfunction "1_1") (pintype "passive"))
      (node (ref "U13N") (pin "B1") (pinfunction "MODE_B1") (pintype "passive"))
    )
    (net (code "38") (name "P2.5V_VGEN5") (class "Default")
      (node (ref "Q11N") (pin "1") (pinfunction "G_1") (pintype "passive"))
    )
    (net (code "39") (name "P2.8V_VGEN6") (class "Default")
      (node (ref "Q13N") (pin "1") (pinfunction "G_1") (pintype "passive"))
    )
    (net (code "40") (name "P3.3V") (class "Default")
      (node (ref "C28N") (pin "1") (pinfunction "1_1") (pintype "passive"))
      (node (ref "C29N") (pin "1") (pinfunction "1_1") (pintype "passive"))
      (node (ref "C30N") (pin "1") (pinfunction "1_1") (pintype "passive"))
      (node (ref "L11N") (pin "2") (pinfunction "2_2") (pintype "passive"))
      (node (ref "Q12N") (pin "1") (pinfunction "S_1") (pintype "passive"))
      (node (ref "Q12N") (pin "2") (pinfunction "S_2") (pintype "passive"))
      (node (ref "Q12N") (pin "3") (pinfunction "S_3") (pintype "passive"))
      (node (ref "R35N") (pin "2") (pinfunction "2_2") (pintype "passive"))
      (node (ref "R36N") (pin "1") (pinfunction "1_1") (pintype "passive"))
      (node (ref "U13N") (pin "A4") (pinfunction "VOUT_A4") (pintype "passive"))
    )
    (net (code "41") (name "P3.3V_DELAYED") (class "Default")
      (node (ref "Q12N") (pin "5") (pinfunction "D_5") (pintype "passive"))
      (node (ref "Q12N") (pin "6") (pinfunction "D_6") (pintype "passive"))
      (node (ref "Q12N") (pin "7") (pinfunction "D_7") (pintype "passive"))
      (node (ref "Q12N") (pin "8") (pinfunction "D_8") (pintype "passive"))
      (node (ref "R28N") (pin "1") (pinfunction "1_1") (pintype "passive"))
      (node (ref "R30N") (pin "1") (pinfunction "1_1") (pintype "passive"))
    )
    (net (code "42") (name "P5.0V") (class "Default")
      (node (ref "C20N") (pin "1") (pinfunction "1_1") (pintype "passive"))
      (node (ref "C21N") (pin "1") (pinfunction "1_1") (pintype "passive"))
      (node (ref "C22N") (pin "1") (pinfunction "1_1") (pintype "passive"))
      (node (ref "C23N") (pin "1") (pinfunction "1_1") (pintype "passive"))
      (node (ref "C27N") (pin "1") (pinfunction "1_1") (pintype "passive"))
      (node (ref "C31N") (pin "1") (pinfunction "1_1") (pintype "passive"))
      (node (ref "C32N") (pin "1") (pinfunction "1_1") (pintype "passive"))
      (node (ref "C33N") (pin "1") (pinfunction "1_1") (pintype "passive"))
      (node (ref "L10N") (pin "2") (pinfunction "2_2") (pintype "passive"))
      (node (ref "L10NB") (pin "2") (pinfunction "2_2") (pintype "passive"))
      (node (ref "Q10N") (pin "1") (pinfunction "S_1") (pintype "passive"))
      (node (ref "Q10N") (pin "2") (pinfunction "S_2") (pintype "passive"))
      (node (ref "Q10N") (pin "3") (pinfunction "S_3") (pintype "passive"))
      (node (ref "R13N") (pin "2") (pinfunction "2_2") (pintype "passive"))
      (node (ref "R24N") (pin "2") (pinfunction "2_2") (pintype "passive"))
      (node (ref "R32N") (pin "1") (pinfunction "1_1") (pintype "passive"))
      (node (ref "R33N") (pin "2") (pinfunction "2_2") (pintype "passive"))
      (node (ref "U13N") (pin "D1") (pinfunction "VIN_D1") (pintype "power_in"))
      (node (ref "U13N") (pin "D2") (pinfunction "VIN_D2") (pintype "power_in"))
      (node (ref "U13N") (pin "E1") (pinfunction "VIN_E1") (pintype "power_in"))
      (node (ref "U13N") (pin "E2") (pinfunction "VIN_E2") (pintype "power_in"))
      (node (ref "U14N") (pin "3") (pinfunction "VCC_3") (pintype "power_in"))
    )
    (net (code "43") (name "P5.0V_DELAYED") (class "Default")
      (node (ref "Q10N") (pin "5") (pinfunction "D_5") (pintype "passive"))
      (node (ref "Q10N") (pin "6") (pinfunction "D_6") (pintype "passive"))
      (node (ref "Q10N") (pin "7") (pinfunction "D_7") (pintype "passive"))
      (node (ref "Q10N") (pin "8") (pinfunction "D_8") (pintype "passive"))
    )
    (net (code "44") (name "unconnected-(J10N-+3.3V-Pad13)") (class "Default")
      (node (ref "J10N") (pin "13") (pinfunction "+3.3V_13") (pintype "power_in+no_connect"))
    )
    (net (code "45") (name "unconnected-(J10N-+5V-Pad7)") (class "Default")
      (node (ref "J10N") (pin "7") (pinfunction "+5V_7") (pintype "power_in+no_connect"))
    )
    (net (code "46") (name "unconnected-(J10N-+5V-Pad8)") (class "Default")
      (node (ref "J10N") (pin "8") (pinfunction "+5V_8") (pintype "power_in+no_connect"))
    )
    (net (code "47") (name "unconnected-(J10N-+5V-Pad9)") (class "Default")
      (node (ref "J10N") (pin "9") (pinfunction "+5V_9") (pintype "power_in+no_connect"))
    )
  )
)
